# programmer.net
KiCad netlist of a schematic drawn in Altium Designer
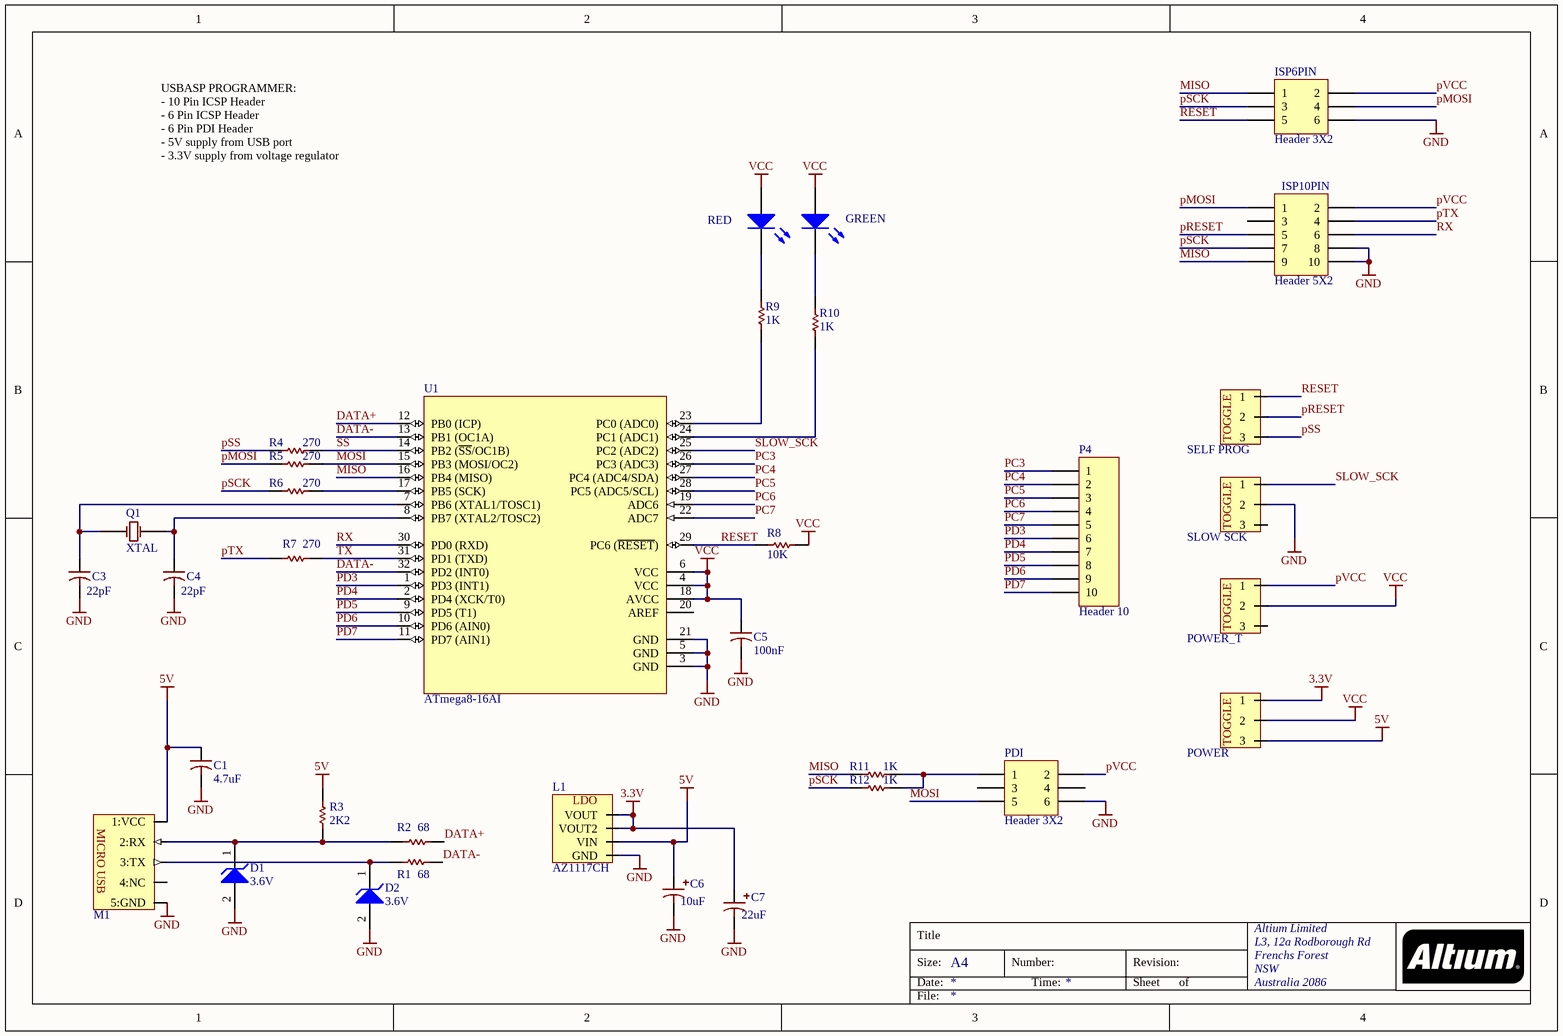
[diagram p0: programmer.SchDoc]

(export (version "E")
  (design (tool "Eeschema 10.0.6"))
  (components
    (comp (ref "C1")
      (value "4.7uF")
      (footprint "CAP4")
      (description "Capacitor - Imperial Units")
      (fields (field (name "Comment") "CAP") (field (name "PUBLISHER") "Altium Limited"))
      (libsource (lib "rmelo19-library") (part "CAP"))
    )
    (comp (ref "C3")
      (value "22pF")
      (footprint "0805")
      (description "Capacitor - Imperial Units")
      (fields (field (name "Comment") "CAP") (field (name "PUBLISHER") "Altium Limited"))
      (libsource (lib "rmelo19-library") (part "CAP"))
    )
    (comp (ref "C4")
      (value "22pF")
      (footprint "0805")
      (description "Capacitor - Imperial Units")
      (fields (field (name "Comment") "CAP") (field (name "PUBLISHER") "Altium Limited"))
      (libsource (lib "rmelo19-library") (part "CAP"))
    )
    (comp (ref "C5")
      (value "100nF")
      (footprint "0805")
      (description "Capacitor - Imperial Units")
      (fields (field (name "Comment") "CAP") (field (name "PUBLISHER") "Altium Limited"))
      (libsource (lib "rmelo19-library") (part "CAP"))
    )
    (comp (ref "C6")
      (value "10uF")
      (footprint "CAP5")
      (description "Aluminum Capacitor - Imperial Units")
      (fields (field (name "Comment") "CAP5") (field (name "PUBLISHER") "Altium Limited"))
      (libsource (lib "rmelo19-library") (part "CAP5"))
    )
    (comp (ref "C7")
      (value "22uF")
      (footprint "CAP5")
      (description "Aluminum Capacitor - Imperial Units")
      (fields (field (name "Comment") "CAP5") (field (name "PUBLISHER") "Altium Limited"))
      (libsource (lib "rmelo19-library") (part "CAP5"))
    )
    (comp (ref "D1")
      (value "3.6V")
      (footprint "ONSC-SOD-123-2-425-04_V")
      (description "Zener Voltage Regulator, 500 mW, 2-Pin SOD-123, Pb-Free, Tape and Reel")
      (fields (field (name "MANUFACTURER") "On Semiconductor") (field (name "PARTNUMBER") "MMSZ4685T1G"))
      (libsource (lib "ON Semi Zener Diodes") (part "MMSZ4685T1G"))
    )
    (comp (ref "D2")
      (value "3.6V")
      (footprint "ONSC-SOD-123-2-425-04_V")
      (description "Zener Voltage Regulator, 500 mW, 2-Pin SOD-123, Pb-Free, Tape and Reel")
      (fields (field (name "MANUFACTURER") "On Semiconductor") (field (name "PARTNUMBER") "MMSZ4685T1G"))
      (libsource (lib "ON Semi Zener Diodes") (part "MMSZ4685T1G"))
    )
    (comp (ref "GREEN")
      (value "LED3")
      (footprint "3.5X2.8X1.9")
      (description "Typical BLUE SiC LED")
      (fields (field (name "PUBLISHER") "Altium Limited"))
      (libsource (lib "Miscellaneous Devices") (part "LED3"))
    )
    (comp (ref "ISP6PIN")
      (value "Header 3X2")
      (footprint "HDR2X3")
      (description "Header, 3-Pin, Dual row")
      (fields (field (name "PUBLISHER") "Altium Limited"))
      (libsource (lib "Miscellaneous Connectors") (part "Header 3X2"))
    )
    (comp (ref "ISP10PIN")
      (value "Header 5X2")
      (footprint "HDR2X5")
      (description "Header, 5-Pin, Dual row")
      (fields (field (name "PUBLISHER") "Altium Limited"))
      (libsource (lib "Miscellaneous Connectors") (part "Header 5X2"))
    )
    (comp (ref "L1")
      (value "AZ1117CH")
      (footprint "SOT-223-DB3_L")
      (description "Low Dropout Voltage Regulator - Imperial Units")
      (libsource (lib "rmelo19-library") (part "AZ1117CH"))
    )
    (comp (ref "M1")
      (value "uUSB_I")
      (footprint "MICROUSB_B")
      (description "Micro USB Type B - Imperial Units")
      (libsource (lib "rmelo19-library") (part "uUSB_I"))
    )
    (comp (ref "P4")
      (value "Header 10")
      (footprint "HDR1X10")
      (description "Header, 10-Pin")
      (fields (field (name "PUBLISHER") "Altium Limited"))
      (libsource (lib "Miscellaneous Connectors") (part "Header 10"))
    )
    (comp (ref "PDI")
      (value "Header 3X2")
      (footprint "HDR2X3")
      (description "Header, 3-Pin, Dual row")
      (fields (field (name "PUBLISHER") "Altium Limited"))
      (libsource (lib "Miscellaneous Connectors") (part "Header 3X2"))
    )
    (comp (ref "POWER")
      (value "TOGGLE SWITCH")
      (footprint "TOGGLE SWITCH")
      (description "Toggle Switch - Imperial Units")
      (libsource (lib "rmelo19-library") (part "TOGGLE SWITCH"))
    )
    (comp (ref "POWER_T")
      (value "TOGGLE SWITCH")
      (footprint "TOGGLE SWITCH")
      (description "Toggle Switch - Imperial Units")
      (libsource (lib "rmelo19-library") (part "TOGGLE SWITCH"))
    )
    (comp (ref "Q1")
      (value "XTAL")
      (footprint "CRYSTAL")
      (description "Crystal Oscillator - Imperial Units")
      (fields (field (name "PUBLISHER") "Altium Limited"))
      (libsource (lib "rmelo19-library") (part "XTAL"))
    )
    (comp (ref "R1")
      (value "68")
      (footprint "0805")
      (description "Resistor - Imperial Units")
      (fields (field (name "Comment") "RES") (field (name "PUBLISHER") "Altium Limited"))
      (libsource (lib "rmelo19-library") (part "RES"))
    )
    (comp (ref "R2")
      (value "68")
      (footprint "0805")
      (description "Resistor - Imperial Units")
      (fields (field (name "Comment") "RES") (field (name "PUBLISHER") "Altium Limited"))
      (libsource (lib "rmelo19-library") (part "RES"))
    )
    (comp (ref "R3")
      (value "2K2")
      (footprint "0805")
      (description "Resistor - Imperial Units")
      (fields (field (name "Comment") "RES") (field (name "PUBLISHER") "Altium Limited"))
      (libsource (lib "rmelo19-library") (part "RES"))
    )
    (comp (ref "R4")
      (value "270")
      (footprint "0805")
      (description "Resistor - Imperial Units")
      (fields (field (name "Comment") "RES") (field (name "PUBLISHER") "Altium Limited"))
      (libsource (lib "rmelo19-library") (part "RES"))
    )
    (comp (ref "R5")
      (value "270")
      (footprint "0805")
      (description "Resistor - Imperial Units")
      (fields (field (name "Comment") "RES") (field (name "PUBLISHER") "Altium Limited"))
      (libsource (lib "rmelo19-library") (part "RES"))
    )
    (comp (ref "R6")
      (value "270")
      (footprint "0805")
      (description "Resistor - Imperial Units")
      (fields (field (name "Comment") "RES") (field (name "PUBLISHER") "Altium Limited"))
      (libsource (lib "rmelo19-library") (part "RES"))
    )
    (comp (ref "R7")
      (value "270")
      (footprint "0805")
      (description "Resistor - Imperial Units")
      (fields (field (name "Comment") "RES") (field (name "PUBLISHER") "Altium Limited"))
      (libsource (lib "rmelo19-library") (part "RES"))
    )
    (comp (ref "R8")
      (value "10K")
      (footprint "0805")
      (description "Resistor - Imperial Units")
      (fields (field (name "Comment") "RES") (field (name "PUBLISHER") "Altium Limited"))
      (libsource (lib "rmelo19-library") (part "RES"))
    )
    (comp (ref "R9")
      (value "1K")
      (footprint "0805")
      (description "Resistor - Imperial Units")
      (fields (field (name "Comment") "RES") (field (name "PUBLISHER") "Altium Limited"))
      (libsource (lib "rmelo19-library") (part "RES"))
    )
    (comp (ref "R10")
      (value "1K")
      (footprint "0805")
      (description "Resistor - Imperial Units")
      (fields (field (name "Comment") "RES") (field (name "PUBLISHER") "Altium Limited"))
      (libsource (lib "rmelo19-library") (part "RES"))
    )
    (comp (ref "R11")
      (value "1K")
      (footprint "0805")
      (description "Resistor - Imperial Units")
      (fields (field (name "Comment") "RES") (field (name "PUBLISHER") "Altium Limited"))
      (libsource (lib "rmelo19-library") (part "RES"))
    )
    (comp (ref "R12")
      (value "1K")
      (footprint "0805")
      (description "Resistor - Imperial Units")
      (fields (field (name "Comment") "RES") (field (name "PUBLISHER") "Altium Limited"))
      (libsource (lib "rmelo19-library") (part "RES"))
    )
    (comp (ref "RED")
      (value "LED3")
      (footprint "3.5X2.8X1.9")
      (description "Typical BLUE SiC LED")
      (fields (field (name "PUBLISHER") "Altium Limited"))
      (libsource (lib "Miscellaneous Devices") (part "LED3"))
    )
    (comp (ref "SELF PROG")
      (value "TOGGLE SWITCH")
      (footprint "TOGGLE SWITCH")
      (description "Toggle Switch - Imperial Units")
      (libsource (lib "rmelo19-library") (part "TOGGLE SWITCH"))
    )
    (comp (ref "SLOW SCK")
      (value "TOGGLE SWITCH")
      (footprint "TOGGLE SWITCH")
      (description "Toggle Switch - Imperial Units")
      (libsource (lib "rmelo19-library") (part "TOGGLE SWITCH"))
    )
    (comp (ref "U1")
      (value "ATmega8-16AI")
      (footprint "32A_N")
      (description "8-Bit AVR Microcontroller with 8K Bytes of In-System Programmable Flash Memory")
      (fields (field (name "PUBLISHER") "Altium Limited"))
      (libsource (lib "Atmel Microcontroller 8-Bit AVR") (part "ATmega8-16AI"))
    )
  )
  (nets
    (net (code "1") (name "/DATA+") (class "Default")
      (node (ref "R2") (pin "2") (pinfunction "2_2") (pintype "passive"))
      (node (ref "U1") (pin "12") (pinfunction "PB0_(ICP)_12") (pintype "bidirectional"))
    )
    (net (code "2") (name "/DATA-") (class "Default")
      (node (ref "R1") (pin "2") (pinfunction "2_2") (pintype "passive"))
      (node (ref "U1") (pin "13") (pinfunction "PB1_(OC1A)_13") (pintype "bidirectional"))
      (node (ref "U1") (pin "32") (pinfunction "PD2_(INT0)_32") (pintype "bidirectional"))
    )
    (net (code "3") (name "/MISO") (class "Default")
      (node (ref "ISP10PIN") (pin "9") (pinfunction "9_9") (pintype "passive"))
      (node (ref "ISP6PIN") (pin "1") (pinfunction "1_1") (pintype "passive"))
      (node (ref "R11") (pin "2") (pinfunction "2_2") (pintype "passive"))
      (node (ref "U1") (pin "16") (pinfunction "PB4_(MISO)_16") (pintype "bidirectional"))
    )
    (net (code "4") (name "/MOSI") (class "Default")
      (node (ref "PDI") (pin "5") (pinfunction "5_5") (pintype "passive"))
      (node (ref "R5") (pin "2") (pinfunction "2_2") (pintype "passive"))
      (node (ref "U1") (pin "15") (pinfunction "PB3_(MOSI/OC2)_15") (pintype "bidirectional"))
    )
    (net (code "5") (name "/PC3") (class "Default")
      (node (ref "P4") (pin "1") (pinfunction "1_1") (pintype "passive"))
      (node (ref "U1") (pin "26") (pinfunction "PC3_(ADC3)_26") (pintype "bidirectional"))
    )
    (net (code "6") (name "/PC4") (class "Default")
      (node (ref "P4") (pin "2") (pinfunction "2_2") (pintype "passive"))
      (node (ref "U1") (pin "27") (pinfunction "PC4_(ADC4/SDA)_27") (pintype "bidirectional"))
    )
    (net (code "7") (name "/PC5") (class "Default")
      (node (ref "P4") (pin "3") (pinfunction "3_3") (pintype "passive"))
      (node (ref "U1") (pin "28") (pinfunction "PC5_(ADC5/SCL)_28") (pintype "bidirectional"))
    )
    (net (code "8") (name "/PC6") (class "Default")
      (node (ref "P4") (pin "4") (pinfunction "4_4") (pintype "passive"))
      (node (ref "U1") (pin "19") (pinfunction "ADC6_19") (pintype "input"))
    )
    (net (code "9") (name "/PC7") (class "Default")
      (node (ref "P4") (pin "5") (pinfunction "5_5") (pintype "passive"))
      (node (ref "U1") (pin "22") (pinfunction "ADC7_22") (pintype "input"))
    )
    (net (code "10") (name "/PD3") (class "Default")
      (node (ref "P4") (pin "6") (pinfunction "6_6") (pintype "passive"))
      (node (ref "U1") (pin "1") (pinfunction "PD3_(INT1)_1") (pintype "bidirectional"))
    )
    (net (code "11") (name "/PD4") (class "Default")
      (node (ref "P4") (pin "7") (pinfunction "7_7") (pintype "passive"))
      (node (ref "U1") (pin "2") (pinfunction "PD4_(XCK/T0)_2") (pintype "bidirectional"))
    )
    (net (code "12") (name "/PD5") (class "Default")
      (node (ref "P4") (pin "8") (pinfunction "8_8") (pintype "passive"))
      (node (ref "U1") (pin "9") (pinfunction "PD5_(T1)_9") (pintype "bidirectional"))
    )
    (net (code "13") (name "/PD6") (class "Default")
      (node (ref "P4") (pin "9") (pinfunction "9_9") (pintype "passive"))
      (node (ref "U1") (pin "10") (pinfunction "PD6_(AIN0)_10") (pintype "bidirectional"))
    )
    (net (code "14") (name "/PD7") (class "Default")
      (node (ref "P4") (pin "10") (pinfunction "10_10") (pintype "passive"))
      (node (ref "U1") (pin "11") (pinfunction "PD7_(AIN1)_11") (pintype "bidirectional"))
    )
    (net (code "15") (name "/RESET") (class "Default")
      (node (ref "ISP6PIN") (pin "5") (pinfunction "5_5") (pintype "passive"))
      (node (ref "R8") (pin "1") (pinfunction "1_1") (pintype "passive"))
      (node (ref "SELF PROG") (pin "1") (pinfunction "1_1") (pintype "passive"))
      (node (ref "U1") (pin "29") (pinfunction "PC6_(~{RESET})_29") (pintype "bidirectional"))
    )
    (net (code "16") (name "/RX") (class "Default")
      (node (ref "ISP10PIN") (pin "6") (pinfunction "6_6") (pintype "passive"))
      (node (ref "U1") (pin "30") (pinfunction "PD0_(RXD)_30") (pintype "bidirectional"))
    )
    (net (code "17") (name "/SLOW_SCK") (class "Default")
      (node (ref "SLOW SCK") (pin "1") (pinfunction "1_1") (pintype "passive"))
      (node (ref "U1") (pin "25") (pinfunction "PC2_(ADC2)_25") (pintype "bidirectional"))
    )
    (net (code "18") (name "/SS") (class "Default")
      (node (ref "R4") (pin "2") (pinfunction "2_2") (pintype "passive"))
      (node (ref "U1") (pin "14") (pinfunction "PB2_(~{SS}/OC1B)_14") (pintype "bidirectional"))
    )
    (net (code "19") (name "/TX") (class "Default")
      (node (ref "R7") (pin "2") (pinfunction "2_2") (pintype "passive"))
      (node (ref "U1") (pin "31") (pinfunction "PD1_(TXD)_31") (pintype "bidirectional"))
    )
    (net (code "20") (name "/pMOSI") (class "Default")
      (node (ref "ISP10PIN") (pin "1") (pinfunction "1_1") (pintype "passive"))
      (node (ref "ISP6PIN") (pin "4") (pinfunction "4_4") (pintype "passive"))
      (node (ref "R5") (pin "1") (pinfunction "1_1") (pintype "passive"))
    )
    (net (code "21") (name "/pRESET") (class "Default")
      (node (ref "ISP10PIN") (pin "5") (pinfunction "5_5") (pintype "passive"))
      (node (ref "SELF PROG") (pin "2") (pinfunction "2_2") (pintype "passive"))
    )
    (net (code "22") (name "/pSCK") (class "Default")
      (node (ref "ISP10PIN") (pin "7") (pinfunction "7_7") (pintype "passive"))
      (node (ref "ISP6PIN") (pin "3") (pinfunction "3_3") (pintype "passive"))
      (node (ref "R12") (pin "2") (pinfunction "2_2") (pintype "passive"))
      (node (ref "R6") (pin "1") (pinfunction "1_1") (pintype "passive"))
    )
    (net (code "23") (name "/pSS") (class "Default")
      (node (ref "R4") (pin "1") (pinfunction "1_1") (pintype "passive"))
      (node (ref "SELF PROG") (pin "3") (pinfunction "3_3") (pintype "passive"))
    )
    (net (code "24") (name "/pTX") (class "Default")
      (node (ref "ISP10PIN") (pin "4") (pinfunction "4_4") (pintype "passive"))
      (node (ref "R7") (pin "1") (pinfunction "1_1") (pintype "passive"))
    )
    (net (code "25") (name "/pVCC") (class "Default")
      (node (ref "ISP10PIN") (pin "2") (pinfunction "2_2") (pintype "passive"))
      (node (ref "ISP6PIN") (pin "2") (pinfunction "2_2") (pintype "passive"))
      (node (ref "PDI") (pin "2") (pinfunction "2_2") (pintype "passive"))
      (node (ref "POWER_T") (pin "1") (pinfunction "1_1") (pintype "passive"))
    )
    (net (code "26") (name "3.3V") (class "Default")
      (node (ref "C7") (pin "2") (pinfunction "2_2") (pintype "passive"))
      (node (ref "L1") (pin "VOUT") (pinfunction "VOUT_VOUT") (pintype "passive"))
      (node (ref "L1") (pin "VOUT2") (pinfunction "VOUT2_VOUT2") (pintype "passive"))
      (node (ref "POWER") (pin "1") (pinfunction "1_1") (pintype "passive"))
    )
    (net (code "27") (name "5V") (class "Default")
      (node (ref "C1") (pin "1") (pinfunction "1_1") (pintype "passive"))
      (node (ref "C6") (pin "2") (pinfunction "2_2") (pintype "passive"))
      (node (ref "L1") (pin "VIN") (pinfunction "VIN_VIN") (pintype "passive"))
      (node (ref "M1") (pin "0") (pinfunction "1:VCC_0") (pintype "power_in"))
      (node (ref "POWER") (pin "3") (pinfunction "3_3") (pintype "passive"))
      (node (ref "R3") (pin "1") (pinfunction "1_1") (pintype "passive"))
    )
    (net (code "28") (name "GND") (class "Default")
      (node (ref "C1") (pin "2") (pinfunction "2_2") (pintype "passive"))
      (node (ref "C3") (pin "2") (pinfunction "2_2") (pintype "passive"))
      (node (ref "C4") (pin "2") (pinfunction "2_2") (pintype "passive"))
      (node (ref "C5") (pin "2") (pinfunction "2_2") (pintype "passive"))
      (node (ref "C6") (pin "1") (pinfunction "1_1") (pintype "passive"))
      (node (ref "C7") (pin "1") (pinfunction "1_1") (pintype "passive"))
      (node (ref "D1") (pin "2") (pinfunction "A_2") (pintype "passive"))
      (node (ref "D2") (pin "2") (pinfunction "A_2") (pintype "passive"))
      (node (ref "ISP10PIN") (pin "10") (pinfunction "10_10") (pintype "passive"))
      (node (ref "ISP10PIN") (pin "8") (pinfunction "8_8") (pintype "passive"))
      (node (ref "ISP6PIN") (pin "6") (pinfunction "6_6") (pintype "passive"))
      (node (ref "L1") (pin "GND") (pinfunction "GND_GND") (pintype "passive"))
      (node (ref "M1") (pin "4") (pinfunction "5:GND_4") (pintype "power_in"))
      (node (ref "PDI") (pin "6") (pinfunction "6_6") (pintype "passive"))
      (node (ref "SLOW SCK") (pin "2") (pinfunction "2_2") (pintype "passive"))
      (node (ref "U1") (pin "21") (pinfunction "GND_21") (pintype "power_in"))
      (node (ref "U1") (pin "3") (pinfunction "GND_3") (pintype "power_in"))
      (node (ref "U1") (pin "5") (pinfunction "GND_5") (pintype "power_in"))
    )
    (net (code "29") (name "Net-(D1-K)") (class "Default")
      (node (ref "D1") (pin "1") (pinfunction "K_1") (pintype "passive"))
      (node (ref "M1") (pin "1") (pinfunction "2:RX_1") (pintype "input"))
      (node (ref "R2") (pin "1") (pinfunction "1_1") (pintype "passive"))
      (node (ref "R3") (pin "2") (pinfunction "2_2") (pintype "passive"))
    )
    (net (code "30") (name "Net-(D2-K)") (class "Default")
      (node (ref "D2") (pin "1") (pinfunction "K_1") (pintype "passive"))
      (node (ref "M1") (pin "2") (pinfunction "3:TX_2") (pintype "output"))
      (node (ref "R1") (pin "1") (pinfunction "1_1") (pintype "passive"))
    )
    (net (code "31") (name "Net-(GREEN-K)") (class "Default")
      (node (ref "GREEN") (pin "2") (pinfunction "K_2") (pintype "passive"))
      (node (ref "R10") (pin "1") (pinfunction "1_1") (pintype "passive"))
    )
    (net (code "32") (name "Net-(PDI-Pad1)") (class "Default")
      (node (ref "PDI") (pin "1") (pinfunction "1_1") (pintype "passive"))
      (node (ref "R11") (pin "1") (pinfunction "1_1") (pintype "passive"))
      (node (ref "R12") (pin "1") (pinfunction "1_1") (pintype "passive"))
    )
    (net (code "33") (name "Net-(Q1-OSC1)") (class "Default")
      (node (ref "C3") (pin "1") (pinfunction "1_1") (pintype "passive"))
      (node (ref "Q1") (pin "1") (pinfunction "OSC1_1") (pintype "passive"))
      (node (ref "U1") (pin "7") (pinfunction "PB6_(XTAL1/TOSC1)_7") (pintype "bidirectional"))
    )
    (net (code "34") (name "Net-(Q1-OSC2)") (class "Default")
      (node (ref "C4") (pin "1") (pinfunction "1_1") (pintype "passive"))
      (node (ref "Q1") (pin "2") (pinfunction "OSC2_2") (pintype "passive"))
      (node (ref "U1") (pin "8") (pinfunction "PB7_(XTAL2/TOSC2)_8") (pintype "bidirectional"))
    )
    (net (code "35") (name "Net-(RED-K)") (class "Default")
      (node (ref "R9") (pin "1") (pinfunction "1_1") (pintype "passive"))
      (node (ref "RED") (pin "2") (pinfunction "K_2") (pintype "passive"))
    )
    (net (code "36") (name "Net-(U1-PB5_(SCK))") (class "Default")
      (node (ref "R6") (pin "2") (pinfunction "2_2") (pintype "passive"))
      (node (ref "U1") (pin "17") (pinfunction "PB5_(SCK)_17") (pintype "bidirectional"))
    )
    (net (code "37") (name "Net-(U1-PC0_(ADC0))") (class "Default")
      (node (ref "R9") (pin "2") (pinfunction "2_2") (pintype "passive"))
      (node (ref "U1") (pin "23") (pinfunction "PC0_(ADC0)_23") (pintype "bidirectional"))
    )
    (net (code "38") (name "Net-(U1-PC1_(ADC1))") (class "Default")
      (node (ref "R10") (pin "2") (pinfunction "2_2") (pintype "passive"))
      (node (ref "U1") (pin "24") (pinfunction "PC1_(ADC1)_24") (pintype "bidirectional"))
    )
    (net (code "39") (name "VCC") (class "Default")
      (node (ref "C5") (pin "1") (pinfunction "1_1") (pintype "passive"))
      (node (ref "GREEN") (pin "1") (pinfunction "A_1") (pintype "passive"))
      (node (ref "POWER") (pin "2") (pinfunction "2_2") (pintype "passive"))
      (node (ref "POWER_T") (pin "2") (pinfunction "2_2") (pintype "passive"))
      (node (ref "R8") (pin "2") (pinfunction "2_2") (pintype "passive"))
      (node (ref "RED") (pin "1") (pinfunction "A_1") (pintype "passive"))
      (node (ref "U1") (pin "18") (pinfunction "AVCC_18") (pintype "power_in"))
      (node (ref "U1") (pin "4") (pinfunction "VCC_4") (pintype "power_in"))
      (node (ref "U1") (pin "6") (pinfunction "VCC_6") (pintype "power_in"))
    )
    (net (code "40") (name "unconnected-(ISP10PIN-Pad3)") (class "Default")
      (node (ref "ISP10PIN") (pin "3") (pinfunction "3_3") (pintype "passive"))
    )
    (net (code "41") (name "unconnected-(M1-4:NC-Pad3)") (class "Default")
      (node (ref "M1") (pin "3") (pinfunction "4:NC_3") (pintype "tri_state"))
    )
    (net (code "42") (name "unconnected-(PDI-Pad3)") (class "Default")
      (node (ref "PDI") (pin "3") (pinfunction "3_3") (pintype "passive"))
    )
    (net (code "43") (name "unconnected-(PDI-Pad4)") (class "Default")
      (node (ref "PDI") (pin "4") (pinfunction "4_4") (pintype "passive"))
    )
    (net (code "44") (name "unconnected-(POWER_T-Pad3)") (class "Default")
      (node (ref "POWER_T") (pin "3") (pinfunction "3_3") (pintype "passive"))
    )
    (net (code "45") (name "unconnected-(SLOW SCK-Pad3)") (class "Default")
      (node (ref "SLOW SCK") (pin "3") (pinfunction "3_3") (pintype "passive"))
    )
    (net (code "46") (name "unconnected-(U1-AREF-Pad20)") (class "Default")
      (node (ref "U1") (pin "20") (pinfunction "AREF_20") (pintype "passive"))
    )
  )
)
